# Display.net
KiCad netlist of a schematic drawn in Altium Designer
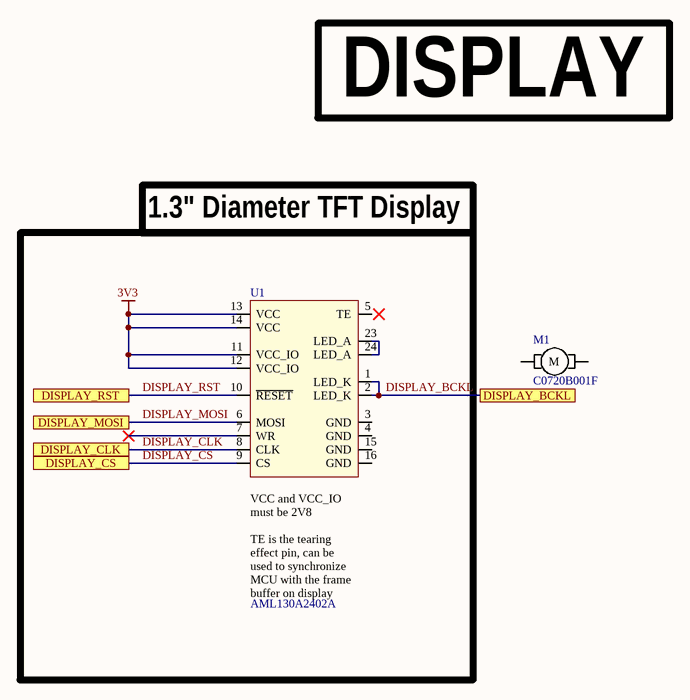
[diagram p0: Display.SchDoc]

(export (version "E")
  (design (tool "Eeschema 10.0.6"))
  (components
    (comp (ref "M1")
      (value "C0720B001F")
      (footprint "C0720B001F")
      (description "DC Motor Vibration, ERM 10000 RPM 3VDC")
      (libsource (lib "smLib") (part "C0720B001F"))
    )
    (comp (ref "U1")
      (value "AML130A2402A")
      (footprint "AML130A2402A")
      (description "AML130A2402A Round 1.3\" TFT Display")
      (libsource (lib "smLib") (part "AML130A2402A"))
    )
  )
  (nets
    (net (code "1") (name "/DISPLAY_BCKL") (class "Default")
      (node (ref "U1") (pin "1") (pinfunction "LED_K_1") (pintype "passive"))
      (node (ref "U1") (pin "2") (pinfunction "LED_K_2") (pintype "passive"))
    )
    (net (code "2") (name "/DISPLAY_CLK") (class "Default")
      (node (ref "U1") (pin "8") (pinfunction "CLK_8") (pintype "passive"))
    )
    (net (code "3") (name "/DISPLAY_CS") (class "Default")
      (node (ref "U1") (pin "9") (pinfunction "CS_9") (pintype "passive"))
    )
    (net (code "4") (name "/DISPLAY_MOSI") (class "Default")
      (node (ref "U1") (pin "6") (pinfunction "MOSI_6") (pintype "passive"))
    )
    (net (code "5") (name "/DISPLAY_RST") (class "Default")
      (node (ref "U1") (pin "10") (pinfunction "~{RESET}_10") (pintype "passive"))
    )
    (net (code "6") (name "3V3") (class "Default")
      (node (ref "U1") (pin "11") (pinfunction "VCC_IO_11") (pintype "passive"))
      (node (ref "U1") (pin "12") (pinfunction "VCC_IO_12") (pintype "passive"))
      (node (ref "U1") (pin "13") (pinfunction "VCC_13") (pintype "passive"))
      (node (ref "U1") (pin "14") (pinfunction "VCC_14") (pintype "passive"))
    )
    (net (code "7") (name "Net-(U1-LED_A-Pad23)") (class "Default")
      (node (ref "U1") (pin "23") (pinfunction "LED_A_23") (pintype "passive"))
      (node (ref "U1") (pin "24") (pinfunction "LED_A_24") (pintype "passive"))
    )
    (net (code "8") (name "unconnected-(M1-Pad1)") (class "Default")
      (node (ref "M1") (pin "1") (pinfunction "1_1") (pintype "passive"))
    )
    (net (code "9") (name "unconnected-(M1-Pad2)") (class "Default")
      (node (ref "M1") (pin "2") (pinfunction "2_2") (pintype "passive"))
    )
    (net (code "10") (name "unconnected-(U1-GND-Pad3)") (class "Default")
      (node (ref "U1") (pin "3") (pinfunction "GND_3") (pintype "passive"))
    )
    (net (code "11") (name "unconnected-(U1-GND-Pad4)") (class "Default")
      (node (ref "U1") (pin "4") (pinfunction "GND_4") (pintype "passive"))
    )
    (net (code "12") (name "unconnected-(U1-GND-Pad15)") (class "Default")
      (node (ref "U1") (pin "15") (pinfunction "GND_15") (pintype "passive"))
    )
    (net (code "13") (name "unconnected-(U1-GND-Pad16)") (class "Default")
      (node (ref "U1") (pin "16") (pinfunction "GND_16") (pintype "passive"))
    )
    (net (code "14") (name "unconnected-(U1-TE-Pad5)") (class "Default")
      (node (ref "U1") (pin "5") (pinfunction "TE_5") (pintype "passive"))
    )
    (net (code "15") (name "unconnected-(U1-WR-Pad7)") (class "Default")
      (node (ref "U1") (pin "7") (pinfunction "WR_7") (pintype "passive+no_connect"))
    )
  )
)
